# Remote.net
KiCad netlist of a schematic drawn in Altium Designer
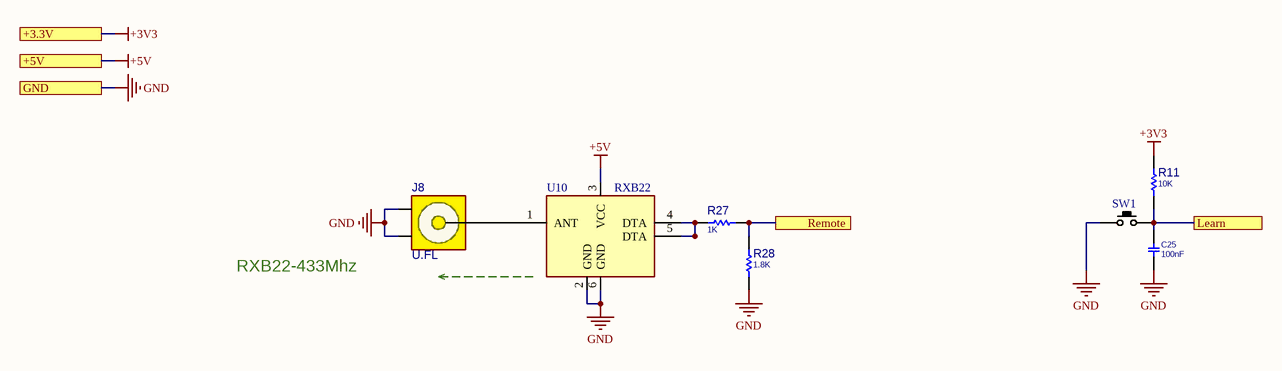
[diagram p0: Remote.SchDoc]

(export (version "E")
  (design (tool "Eeschema 10.0.6"))
  (components
    (comp (ref "C25")
      (value "100nF")
      (footprint "C0805")
      (description "CAP, MLCC, -F, -V, MATERIAL, -%, 0201")
      (fields (field (name "MANF_P#") "MANF_PART#"))
      (libsource (lib "passive_smd") (part "CAP_SMD_MLCC_0805"))
    )
    (comp (ref "J8")
      (value "U.FL")
      (footprint "UFL")
      (description "CONN, RF, U.FL, STRAIGHT, Ultra Miniature Coaxial")
      (fields
        (field (name "MANF_P#") "CONUFL001-SMD, U.FL-R-SMT-1(10), 128-0711-201")
        (field (name "MANF") "Linx, Hirose, Cinch")
      )
      (libsource (lib "conn_rf") (part "CONN_RF_UFL"))
    )
    (comp (ref "R11")
      (value "10K")
      (footprint "R0805")
      (description "RESISTOR, SMD")
      (libsource (lib "passive_smd") (part "RES_SMD_0805"))
    )
    (comp (ref "R27")
      (value "1K")
      (footprint "R0805")
      (description "RESISTOR, SMD")
      (libsource (lib "passive_smd") (part "RES_SMD_0805"))
    )
    (comp (ref "R28")
      (value "1.8K")
      (footprint "R0805")
      (description "RESISTOR, SMD")
      (libsource (lib "passive_smd") (part "RES_SMD_0805"))
    )
    (comp (ref "SW1")
      (value "Tactile Switch")
      (footprint "Tactile Switch")
      (description "3x6x5 mm - 2 Pin")
      (libsource (lib "Mehrdad") (part "Tactile Switch"))
    )
    (comp (ref "U10")
      (value "RXB22")
      (footprint "RXB22")
      (description "RF Receiver 433Mhz")
      (libsource (lib "Mehrdad") (part "RXB22"))
    )
  )
  (nets
    (net (code "1") (name "+3V3") (class "Default")
      (node (ref "R11") (pin "1") (pinfunction "1_1") (pintype "passive"))
    )
    (net (code "2") (name "+5V") (class "Default")
      (node (ref "U10") (pin "3") (pinfunction "VCC_3") (pintype "passive"))
    )
    (net (code "3") (name "/Learn") (class "Default")
      (node (ref "C25") (pin "2") (pinfunction "2_2") (pintype "passive"))
      (node (ref "R11") (pin "2") (pinfunction "2_2") (pintype "passive"))
      (node (ref "SW1") (pin "2") (pinfunction "P3_2") (pintype "passive"))
    )
    (net (code "4") (name "/Remote") (class "Default")
      (node (ref "R27") (pin "2") (pinfunction "2_2") (pintype "passive"))
      (node (ref "R28") (pin "2") (pinfunction "2_2") (pintype "passive"))
    )
    (net (code "5") (name "GND") (class "Default")
      (node (ref "C25") (pin "1") (pinfunction "1_1") (pintype "passive"))
      (node (ref "J8") (pin "2") (pinfunction "G1_2") (pintype "passive"))
      (node (ref "J8") (pin "3") (pinfunction "G2_3") (pintype "passive"))
      (node (ref "R28") (pin "1") (pinfunction "1_1") (pintype "passive"))
      (node (ref "SW1") (pin "1") (pinfunction "P1_1") (pintype "passive"))
      (node (ref "U10") (pin "2") (pinfunction "GND_2") (pintype "passive"))
      (node (ref "U10") (pin "6") (pinfunction "GND_6") (pintype "passive"))
    )
    (net (code "6") (name "Net-(J8-SIG)") (class "Default")
      (node (ref "J8") (pin "1") (pinfunction "SIG_1") (pintype "passive"))
      (node (ref "U10") (pin "1") (pinfunction "ANT_1") (pintype "passive"))
    )
    (net (code "7") (name "Net-(R27-Pad1)") (class "Default")
      (node (ref "R27") (pin "1") (pinfunction "1_1") (pintype "passive"))
      (node (ref "U10") (pin "4") (pinfunction "DTA_4") (pintype "passive"))
      (node (ref "U10") (pin "5") (pinfunction "DTA_5") (pintype "passive"))
    )
  )
)
